# LTC6804-2_BMS_TR.net
KiCad netlist of a schematic drawn in Altium Designer
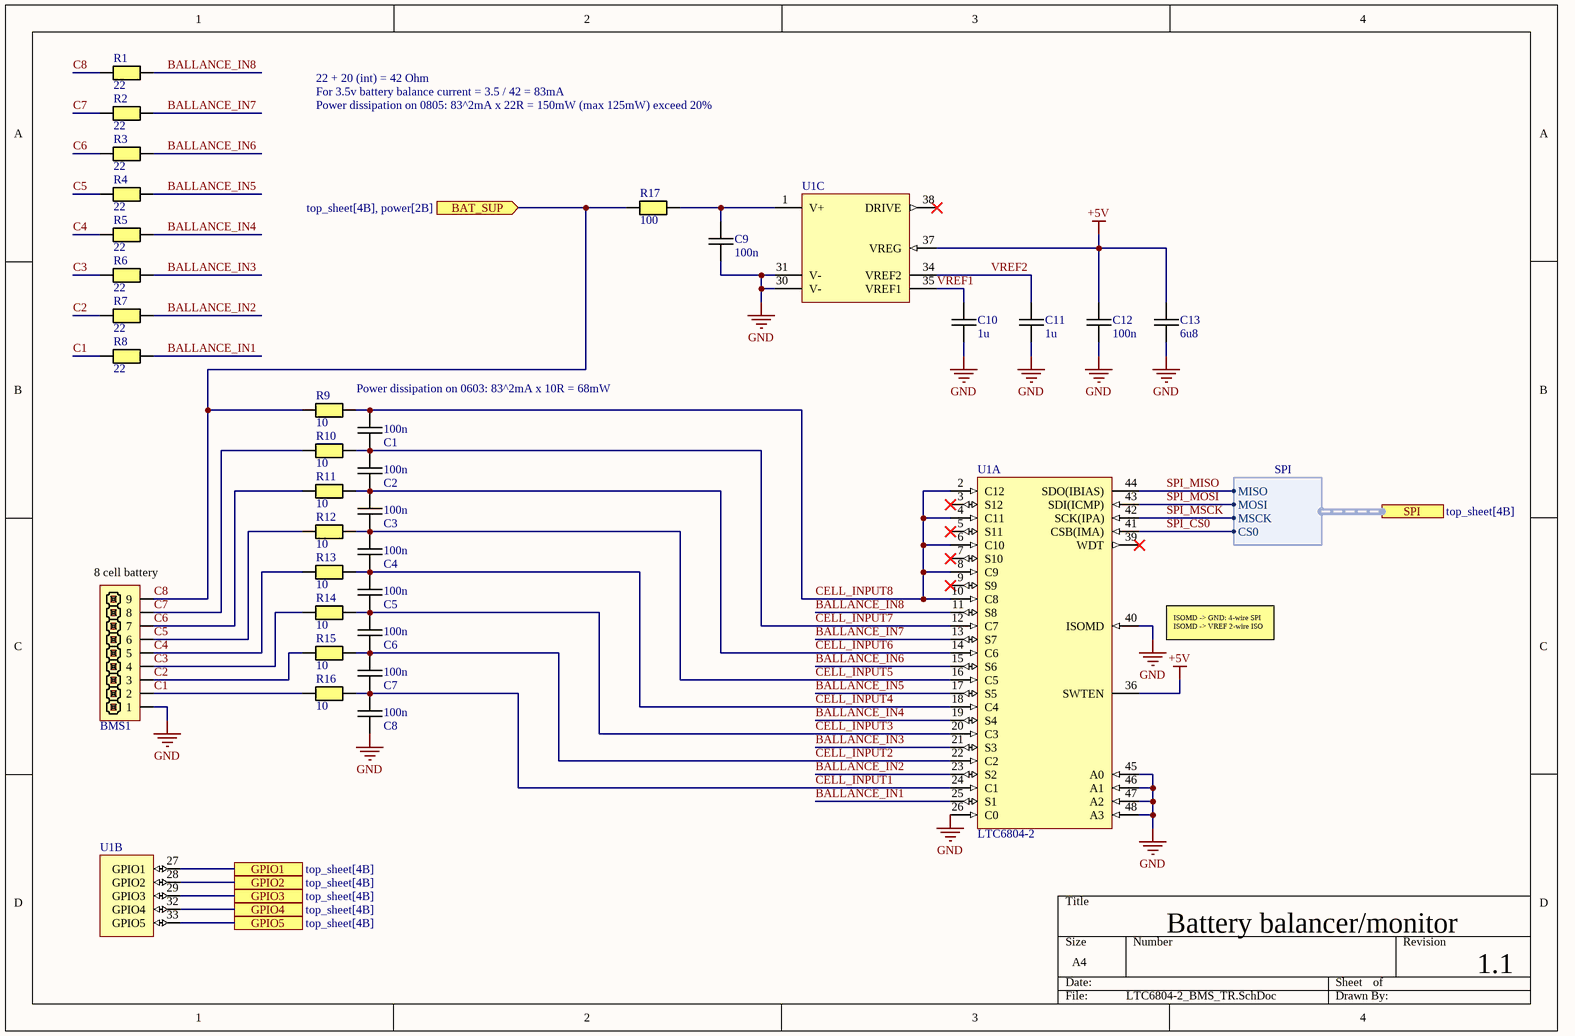
[diagram p0: LTC6804-2_BMS_TR.SchDoc]

(export (version "E")
  (design (tool "Eeschema 10.0.6"))
  (components
    (comp (ref "BMS1")
      (value "PIN HEADER 1x9")
      (footprint "XH2.54 9P")
      (libsource (lib "Connectors") (part "PIN HEADER 2.54 1x9"))
    )
    (comp (ref "C1")
      (value "100n")
      (footprint "CAPC0603(1608)55_N")
      (description "Ceramic capacitor Medium density")
      (libsource (lib "Discrete") (part "Capacitor M"))
    )
    (comp (ref "C2")
      (value "100n")
      (footprint "CAPC0603(1608)55_N")
      (description "Ceramic capacitor Medium density")
      (libsource (lib "Discrete") (part "Capacitor M"))
    )
    (comp (ref "C3")
      (value "100n")
      (footprint "CAPC0603(1608)55_N")
      (description "Ceramic capacitor Medium density")
      (libsource (lib "Discrete") (part "Capacitor M"))
    )
    (comp (ref "C4")
      (value "100n")
      (footprint "CAPC0603(1608)55_N")
      (description "Ceramic capacitor Medium density")
      (libsource (lib "Discrete") (part "Capacitor M"))
    )
    (comp (ref "C5")
      (value "100n")
      (footprint "CAPC0603(1608)55_N")
      (description "Ceramic capacitor Medium density")
      (libsource (lib "Discrete") (part "Capacitor M"))
    )
    (comp (ref "C6")
      (value "100n")
      (footprint "CAPC0603(1608)55_N")
      (description "Ceramic capacitor Medium density")
      (libsource (lib "Discrete") (part "Capacitor M"))
    )
    (comp (ref "C7")
      (value "100n")
      (footprint "CAPC0603(1608)55_N")
      (description "Ceramic capacitor Medium density")
      (libsource (lib "Discrete") (part "Capacitor M"))
    )
    (comp (ref "C8")
      (value "100n")
      (footprint "CAPC0603(1608)55_N")
      (description "Ceramic capacitor Medium density")
      (libsource (lib "Discrete") (part "Capacitor M"))
    )
    (comp (ref "C9")
      (value "100n")
      (footprint "CAPC0603(1608)55_N")
      (description "Ceramic capacitor Medium density")
      (libsource (lib "Discrete") (part "Capacitor M"))
    )
    (comp (ref "C10")
      (value "1u")
      (footprint "CAPC0805(2012)75_N")
      (description "Ceramic capacitor Medium density")
      (libsource (lib "Discrete") (part "Capacitor M"))
    )
    (comp (ref "C11")
      (value "1u")
      (footprint "CAPC0805(2012)75_N")
      (description "Ceramic capacitor Medium density")
      (libsource (lib "Discrete") (part "Capacitor M"))
    )
    (comp (ref "C12")
      (value "100n")
      (footprint "CAPC0603(1608)55_N")
      (description "Ceramic capacitor Medium density")
      (libsource (lib "Discrete") (part "Capacitor M"))
    )
    (comp (ref "C13")
      (value "6u8")
      (footprint "CAPC0805(2012)75_N")
      (description "Ceramic capacitor Medium density")
      (libsource (lib "Discrete") (part "Capacitor M"))
    )
    (comp (ref "R1")
      (value "22")
      (footprint "RESC0805(2012)_N")
      (description "Resistor Medium Density")
      (libsource (lib "Discrete") (part "Resistor M"))
    )
    (comp (ref "R2")
      (value "22")
      (footprint "RESC0805(2012)_N")
      (description "Resistor Medium Density")
      (libsource (lib "Discrete") (part "Resistor M"))
    )
    (comp (ref "R3")
      (value "22")
      (footprint "RESC0805(2012)_N")
      (description "Resistor Medium Density")
      (libsource (lib "Discrete") (part "Resistor M"))
    )
    (comp (ref "R4")
      (value "22")
      (footprint "RESC0805(2012)_N")
      (description "Resistor Medium Density")
      (libsource (lib "Discrete") (part "Resistor M"))
    )
    (comp (ref "R5")
      (value "22")
      (footprint "RESC0805(2012)_N")
      (description "Resistor Medium Density")
      (libsource (lib "Discrete") (part "Resistor M"))
    )
    (comp (ref "R6")
      (value "22")
      (footprint "RESC0805(2012)_N")
      (description "Resistor Medium Density")
      (libsource (lib "Discrete") (part "Resistor M"))
    )
    (comp (ref "R7")
      (value "22")
      (footprint "RESC0805(2012)_N")
      (description "Resistor Medium Density")
      (libsource (lib "Discrete") (part "Resistor M"))
    )
    (comp (ref "R8")
      (value "22")
      (footprint "RESC0805(2012)_N")
      (description "Resistor Medium Density")
      (libsource (lib "Discrete") (part "Resistor M"))
    )
    (comp (ref "R9")
      (value "10")
      (footprint "RESC0603(1608)_N")
      (description "Resistor Medium Density")
      (libsource (lib "Discrete") (part "Resistor M"))
    )
    (comp (ref "R10")
      (value "10")
      (footprint "RESC0603(1608)_N")
      (description "Resistor Medium Density")
      (libsource (lib "Discrete") (part "Resistor M"))
    )
    (comp (ref "R11")
      (value "10")
      (footprint "RESC0603(1608)_N")
      (description "Resistor Medium Density")
      (libsource (lib "Discrete") (part "Resistor M"))
    )
    (comp (ref "R12")
      (value "10")
      (footprint "RESC0603(1608)_N")
      (description "Resistor Medium Density")
      (libsource (lib "Discrete") (part "Resistor M"))
    )
    (comp (ref "R13")
      (value "10")
      (footprint "RESC0603(1608)_N")
      (description "Resistor Medium Density")
      (libsource (lib "Discrete") (part "Resistor M"))
    )
    (comp (ref "R14")
      (value "10")
      (footprint "RESC0603(1608)_N")
      (description "Resistor Medium Density")
      (libsource (lib "Discrete") (part "Resistor M"))
    )
    (comp (ref "R15")
      (value "10")
      (footprint "RESC0603(1608)_N")
      (description "Resistor Medium Density")
      (libsource (lib "Discrete") (part "Resistor M"))
    )
    (comp (ref "R16")
      (value "10")
      (footprint "RESC0603(1608)_N")
      (description "Resistor Medium Density")
      (libsource (lib "Discrete") (part "Resistor M"))
    )
    (comp (ref "R17")
      (value "100")
      (footprint "RESC0603(1608)_N")
      (description "Resistor Medium Density")
      (libsource (lib "Discrete") (part "Resistor M"))
    )
    (comp (ref "U1")
      (value "LTC6804-2")
      (footprint "SSOP48")
      (libsource (lib "IntegrationCircuits") (part "LTC6804-2"))
    )
  )
  (nets
    (net (code "2") (name "+5V") (class "Default")
      (node (ref "C12") (pin "1") (pinfunction "1_1") (pintype "passive"))
      (node (ref "C13") (pin "1") (pinfunction "1_1") (pintype "passive"))
      (node (ref "U1") (pin "36") (pinfunction "SWTEN_36") (pintype "passive"))
      (node (ref "U1") (pin "37") (pinfunction "VREG_37") (pintype "input"))
    )
    (net (code "3") (name "/BALLANCE_IN1") (class "Default")
      (node (ref "R8") (pin "2") (pinfunction "2_2") (pintype "passive"))
      (node (ref "U1") (pin "25") (pinfunction "S1_25") (pintype "bidirectional"))
    )
    (net (code "4") (name "/BALLANCE_IN2") (class "Default")
      (node (ref "R7") (pin "2") (pinfunction "2_2") (pintype "passive"))
      (node (ref "U1") (pin "23") (pinfunction "S2_23") (pintype "bidirectional"))
    )
    (net (code "5") (name "/BALLANCE_IN3") (class "Default")
      (node (ref "R6") (pin "2") (pinfunction "2_2") (pintype "passive"))
      (node (ref "U1") (pin "21") (pinfunction "S3_21") (pintype "bidirectional"))
    )
    (net (code "6") (name "/BALLANCE_IN4") (class "Default")
      (node (ref "R5") (pin "2") (pinfunction "2_2") (pintype "passive"))
      (node (ref "U1") (pin "19") (pinfunction "S4_19") (pintype "bidirectional"))
    )
    (net (code "7") (name "/BALLANCE_IN5") (class "Default")
      (node (ref "R4") (pin "2") (pinfunction "2_2") (pintype "passive"))
      (node (ref "U1") (pin "17") (pinfunction "S5_17") (pintype "bidirectional"))
    )
    (net (code "8") (name "/BALLANCE_IN6") (class "Default")
      (node (ref "R3") (pin "2") (pinfunction "2_2") (pintype "passive"))
      (node (ref "U1") (pin "15") (pinfunction "S6_15") (pintype "bidirectional"))
    )
    (net (code "9") (name "/BALLANCE_IN7") (class "Default")
      (node (ref "R2") (pin "2") (pinfunction "2_2") (pintype "passive"))
      (node (ref "U1") (pin "13") (pinfunction "S7_13") (pintype "bidirectional"))
    )
    (net (code "10") (name "/BALLANCE_IN8") (class "Default")
      (node (ref "R1") (pin "2") (pinfunction "2_2") (pintype "passive"))
      (node (ref "U1") (pin "11") (pinfunction "S8_11") (pintype "bidirectional"))
    )
    (net (code "11") (name "/C1") (class "Default")
      (node (ref "BMS1") (pin "2") (pinfunction "2_2") (pintype "passive"))
      (node (ref "R16") (pin "1") (pinfunction "1_1") (pintype "passive"))
      (node (ref "R8") (pin "1") (pinfunction "1_1") (pintype "passive"))
    )
    (net (code "12") (name "/C2") (class "Default")
      (node (ref "BMS1") (pin "3") (pinfunction "3_3") (pintype "passive"))
      (node (ref "R15") (pin "1") (pinfunction "1_1") (pintype "passive"))
      (node (ref "R7") (pin "1") (pinfunction "1_1") (pintype "passive"))
    )
    (net (code "13") (name "/C3") (class "Default")
      (node (ref "BMS1") (pin "4") (pinfunction "4_4") (pintype "passive"))
      (node (ref "R14") (pin "1") (pinfunction "1_1") (pintype "passive"))
      (node (ref "R6") (pin "1") (pinfunction "1_1") (pintype "passive"))
    )
    (net (code "14") (name "/C4") (class "Default")
      (node (ref "BMS1") (pin "5") (pinfunction "5_5") (pintype "passive"))
      (node (ref "R13") (pin "1") (pinfunction "1_1") (pintype "passive"))
      (node (ref "R5") (pin "1") (pinfunction "1_1") (pintype "passive"))
    )
    (net (code "15") (name "/C5") (class "Default")
      (node (ref "BMS1") (pin "6") (pinfunction "6_6") (pintype "passive"))
      (node (ref "R12") (pin "1") (pinfunction "1_1") (pintype "passive"))
      (node (ref "R4") (pin "1") (pinfunction "1_1") (pintype "passive"))
    )
    (net (code "16") (name "/C6") (class "Default")
      (node (ref "BMS1") (pin "7") (pinfunction "7_7") (pintype "passive"))
      (node (ref "R11") (pin "1") (pinfunction "1_1") (pintype "passive"))
      (node (ref "R3") (pin "1") (pinfunction "1_1") (pintype "passive"))
    )
    (net (code "17") (name "/C7") (class "Default")
      (node (ref "BMS1") (pin "8") (pinfunction "8_8") (pintype "passive"))
      (node (ref "R10") (pin "1") (pinfunction "1_1") (pintype "passive"))
      (node (ref "R2") (pin "1") (pinfunction "1_1") (pintype "passive"))
    )
    (net (code "18") (name "/C8") (class "Default")
      (node (ref "BMS1") (pin "9") (pinfunction "9_9") (pintype "passive"))
      (node (ref "R1") (pin "1") (pinfunction "1_1") (pintype "passive"))
      (node (ref "R17") (pin "1") (pinfunction "1_1") (pintype "passive"))
      (node (ref "R9") (pin "1") (pinfunction "1_1") (pintype "passive"))
    )
    (net (code "19") (name "/CELL_INPUT1") (class "Default")
      (node (ref "C7") (pin "2") (pinfunction "2_2") (pintype "passive"))
      (node (ref "C8") (pin "1") (pinfunction "1_1") (pintype "passive"))
      (node (ref "R16") (pin "2") (pinfunction "2_2") (pintype "passive"))
      (node (ref "U1") (pin "24") (pinfunction "C1_24") (pintype "input"))
    )
    (net (code "20") (name "/CELL_INPUT2") (class "Default")
      (node (ref "C6") (pin "2") (pinfunction "2_2") (pintype "passive"))
      (node (ref "C7") (pin "1") (pinfunction "1_1") (pintype "passive"))
      (node (ref "R15") (pin "2") (pinfunction "2_2") (pintype "passive"))
      (node (ref "U1") (pin "22") (pinfunction "C2_22") (pintype "input"))
    )
    (net (code "21") (name "/CELL_INPUT3") (class "Default")
      (node (ref "C5") (pin "2") (pinfunction "2_2") (pintype "passive"))
      (node (ref "C6") (pin "1") (pinfunction "1_1") (pintype "passive"))
      (node (ref "R14") (pin "2") (pinfunction "2_2") (pintype "passive"))
      (node (ref "U1") (pin "20") (pinfunction "C3_20") (pintype "input"))
    )
    (net (code "22") (name "/CELL_INPUT4") (class "Default")
      (node (ref "C4") (pin "2") (pinfunction "2_2") (pintype "passive"))
      (node (ref "C5") (pin "1") (pinfunction "1_1") (pintype "passive"))
      (node (ref "R13") (pin "2") (pinfunction "2_2") (pintype "passive"))
      (node (ref "U1") (pin "18") (pinfunction "C4_18") (pintype "input"))
    )
    (net (code "23") (name "/CELL_INPUT5") (class "Default")
      (node (ref "C3") (pin "2") (pinfunction "2_2") (pintype "passive"))
      (node (ref "C4") (pin "1") (pinfunction "1_1") (pintype "passive"))
      (node (ref "R12") (pin "2") (pinfunction "2_2") (pintype "passive"))
      (node (ref "U1") (pin "16") (pinfunction "C5_16") (pintype "input"))
    )
    (net (code "24") (name "/CELL_INPUT6") (class "Default")
      (node (ref "C2") (pin "2") (pinfunction "2_2") (pintype "passive"))
      (node (ref "C3") (pin "1") (pinfunction "1_1") (pintype "passive"))
      (node (ref "R11") (pin "2") (pinfunction "2_2") (pintype "passive"))
      (node (ref "U1") (pin "14") (pinfunction "C6_14") (pintype "input"))
    )
    (net (code "25") (name "/CELL_INPUT7") (class "Default")
      (node (ref "C1") (pin "2") (pinfunction "2_2") (pintype "passive"))
      (node (ref "C2") (pin "1") (pinfunction "1_1") (pintype "passive"))
      (node (ref "R10") (pin "2") (pinfunction "2_2") (pintype "passive"))
      (node (ref "U1") (pin "12") (pinfunction "C7_12") (pintype "input"))
    )
    (net (code "26") (name "/CELL_INPUT8") (class "Default")
      (node (ref "C1") (pin "1") (pinfunction "1_1") (pintype "passive"))
      (node (ref "R9") (pin "2") (pinfunction "2_2") (pintype "passive"))
      (node (ref "U1") (pin "10") (pinfunction "C8_10") (pintype "input"))
      (node (ref "U1") (pin "2") (pinfunction "C12_2") (pintype "input"))
      (node (ref "U1") (pin "4") (pinfunction "C11_4") (pintype "input"))
      (node (ref "U1") (pin "6") (pinfunction "C10_6") (pintype "input"))
      (node (ref "U1") (pin "8") (pinfunction "C9_8") (pintype "input"))
    )
    (net (code "27") (name "/GPIO1") (class "Default")
      (node (ref "U1") (pin "27") (pinfunction "GPIO1_27") (pintype "bidirectional"))
    )
    (net (code "28") (name "/GPIO2") (class "Default")
      (node (ref "U1") (pin "28") (pinfunction "GPIO2_28") (pintype "bidirectional"))
    )
    (net (code "29") (name "/GPIO3") (class "Default")
      (node (ref "U1") (pin "29") (pinfunction "GPIO3_29") (pintype "bidirectional"))
    )
    (net (code "30") (name "/GPIO4") (class "Default")
      (node (ref "U1") (pin "32") (pinfunction "GPIO4_32") (pintype "bidirectional"))
    )
    (net (code "31") (name "/GPIO5") (class "Default")
      (node (ref "U1") (pin "33") (pinfunction "GPIO5_33") (pintype "bidirectional"))
    )
    (net (code "32") (name "/SPI_CS0") (class "Default")
      (node (ref "U1") (pin "41") (pinfunction "CSB(IMA)_41") (pintype "input"))
    )
    (net (code "33") (name "/SPI_MISO") (class "Default")
      (node (ref "U1") (pin "44") (pinfunction "SDO(IBIAS)_44") (pintype "open_collector"))
    )
    (net (code "34") (name "/SPI_MOSI") (class "Default")
      (node (ref "U1") (pin "43") (pinfunction "SDI(ICMP)_43") (pintype "input"))
    )
    (net (code "35") (name "/SPI_MSCK") (class "Default")
      (node (ref "U1") (pin "42") (pinfunction "SCK(IPA)_42") (pintype "input"))
    )
    (net (code "36") (name "/VREF1") (class "Default")
      (node (ref "C10") (pin "1") (pinfunction "1_1") (pintype "passive"))
      (node (ref "U1") (pin "35") (pinfunction "VREF1_35") (pintype "power_in"))
    )
    (net (code "37") (name "/VREF2") (class "Default")
      (node (ref "C11") (pin "1") (pinfunction "1_1") (pintype "passive"))
      (node (ref "U1") (pin "34") (pinfunction "VREF2_34") (pintype "power_in"))
    )
    (net (code "39") (name "GND") (class "Default")
      (node (ref "BMS1") (pin "1") (pinfunction "1_1") (pintype "passive"))
      (node (ref "C10") (pin "2") (pinfunction "2_2") (pintype "passive"))
      (node (ref "C11") (pin "2") (pinfunction "2_2") (pintype "passive"))
      (node (ref "C12") (pin "2") (pinfunction "2_2") (pintype "passive"))
      (node (ref "C13") (pin "2") (pinfunction "2_2") (pintype "passive"))
      (node (ref "C8") (pin "2") (pinfunction "2_2") (pintype "passive"))
      (node (ref "C9") (pin "2") (pinfunction "2_2") (pintype "passive"))
      (node (ref "U1") (pin "26") (pinfunction "C0_26") (pintype "input"))
      (node (ref "U1") (pin "30") (pinfunction "V-_30") (pintype "power_in"))
      (node (ref "U1") (pin "31") (pinfunction "V-_31") (pintype "power_in"))
      (node (ref "U1") (pin "40") (pinfunction "ISOMD_40") (pintype "input"))
      (node (ref "U1") (pin "45") (pinfunction "A0_45") (pintype "input"))
      (node (ref "U1") (pin "46") (pinfunction "A1_46") (pintype "input"))
      (node (ref "U1") (pin "47") (pinfunction "A2_47") (pintype "input"))
      (node (ref "U1") (pin "48") (pinfunction "A3_48") (pintype "input"))
    )
    (net (code "40") (name "Net-(U1C-V+)") (class "Default")
      (node (ref "C9") (pin "1") (pinfunction "1_1") (pintype "passive"))
      (node (ref "R17") (pin "2") (pinfunction "2_2") (pintype "passive"))
      (node (ref "U1") (pin "1") (pinfunction "V+_1") (pintype "power_in"))
    )
    (net (code "41") (name "unconnected-(U1A-S9-Pad9)") (class "Default")
      (node (ref "U1") (pin "9") (pinfunction "S9_9") (pintype "bidirectional+no_connect"))
    )
    (net (code "42") (name "unconnected-(U1A-S10-Pad7)") (class "Default")
      (node (ref "U1") (pin "7") (pinfunction "S10_7") (pintype "bidirectional+no_connect"))
    )
    (net (code "43") (name "unconnected-(U1A-S11-Pad5)") (class "Default")
      (node (ref "U1") (pin "5") (pinfunction "S11_5") (pintype "bidirectional+no_connect"))
    )
    (net (code "44") (name "unconnected-(U1A-S12-Pad3)") (class "Default")
      (node (ref "U1") (pin "3") (pinfunction "S12_3") (pintype "bidirectional+no_connect"))
    )
    (net (code "45") (name "unconnected-(U1A-WDT-Pad39)") (class "Default")
      (node (ref "U1") (pin "39") (pinfunction "WDT_39") (pintype "output+no_connect"))
    )
    (net (code "46") (name "unconnected-(U1C-DRIVE-Pad38)") (class "Default")
      (node (ref "U1") (pin "38") (pinfunction "DRIVE_38") (pintype "output+no_connect"))
    )
  )
)
